# PR2019-DataAcquisitionSystem.net
KiCad netlist of a schematic drawn in Altium Designer
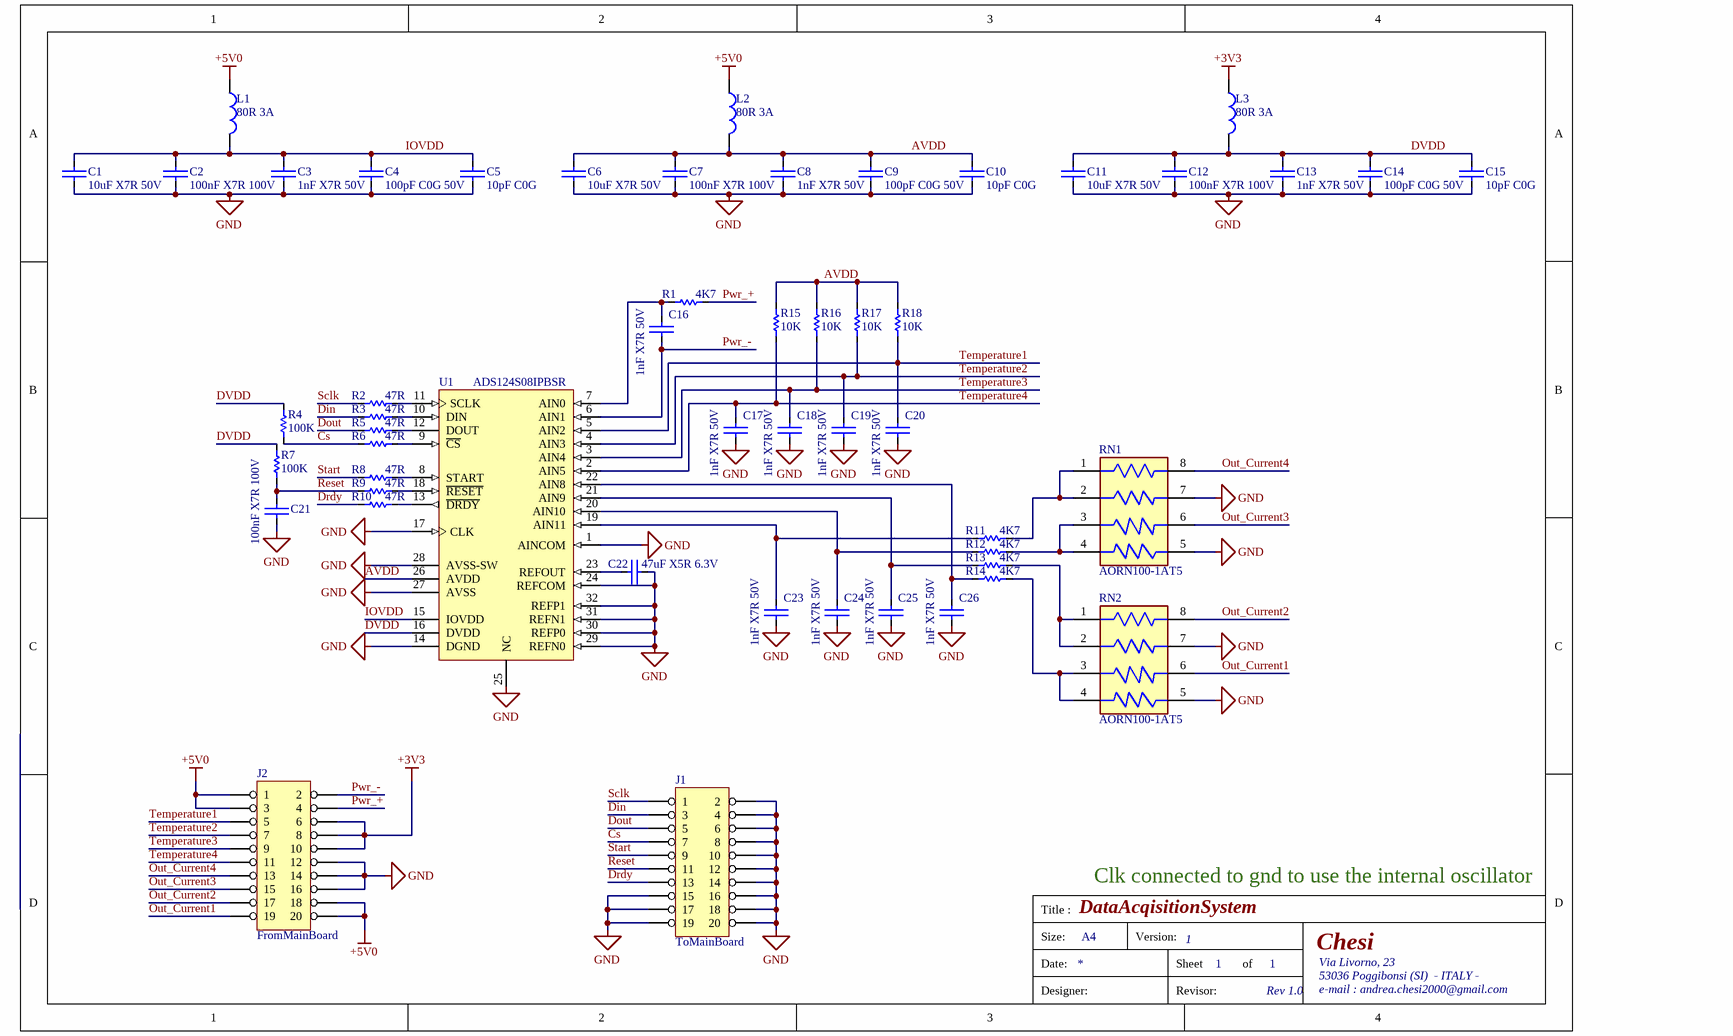
[diagram p0: PR2019-DataAcquisitionSystem.SchDoc]

(export (version "E")
  (design (tool "Eeschema 10.0.6"))
  (components
    (comp (ref "C1")
      (value "10uF X7R 50V")
      (footprint "1206")
      (description "Capacità")
      (fields
        (field (name "1 SUPPLIER PART NUMBER") "CL31B106KBHNNNE")
        (field (name "ARSILICII PART NUMBER") "CPC0232011")
      )
      (libsource (lib "Library_20-02-20") (part "CAP_10uF X7R 50V_1206"))
    )
    (comp (ref "C2")
      (value "100nF X7R 100V")
      (footprint "0805")
      (description "Capacità")
      (fields
        (field (name "1 SUPPLIER PART NUMBER") "CL21B104KCFSFNG")
        (field (name "2 SUPPLIER PART NUMBER") "1907331")
      )
      (libsource (lib "Library_20-02-20") (part "CAP_100nF X7R 100V_0805"))
    )
    (comp (ref "C3")
      (value "1nF X7R 50V")
      (footprint "0805")
      (description "Capacità")
      (fields
        (field (name "1 SUPPLIER PART NUMBER") "B37941K5102K60")
        (field (name "2 SUPPLIER PART NUMBER") "0805B102K5CT")
      )
      (libsource (lib "Library_20-02-20") (part "CAP_1nF X7R 50V_0805"))
    )
    (comp (ref "C4")
      (value "100pF C0G 50V")
      (footprint "0805")
      (description "Capacità")
      (fields
        (field (name "1 SUPPLIER PART NUMBER") "CC0805JRNPO9BN101")
        (field (name "ARSILICII PART NUMBER") "CPC0614100")
      )
      (libsource (lib "Library_20-02-20") (part "CAP_100pF C0G 50V_0805"))
    )
    (comp (ref "C5")
      (value "10pF C0G")
      (footprint "0805")
      (description "Capacità")
      (fields (field (name "ARSILICII PART NUMBER") "CPC0614010"))
      (libsource (lib "Library_20-02-20") (part "CAP_10pF C0G_0805"))
    )
    (comp (ref "C6")
      (value "10uF X7R 50V")
      (footprint "1206")
      (description "Capacità")
      (fields
        (field (name "1 SUPPLIER PART NUMBER") "CL31B106KBHNNNE")
        (field (name "ARSILICII PART NUMBER") "CPC0232011")
      )
      (libsource (lib "Library_20-02-20") (part "CAP_10uF X7R 50V_1206"))
    )
    (comp (ref "C7")
      (value "100nF X7R 100V")
      (footprint "0805")
      (description "Capacità")
      (fields
        (field (name "1 SUPPLIER PART NUMBER") "CL21B104KCFSFNG")
        (field (name "2 SUPPLIER PART NUMBER") "1907331")
      )
      (libsource (lib "Library_20-02-20") (part "CAP_100nF X7R 100V_0805"))
    )
    (comp (ref "C8")
      (value "1nF X7R 50V")
      (footprint "0805")
      (description "Capacità")
      (fields
        (field (name "1 SUPPLIER PART NUMBER") "B37941K5102K60")
        (field (name "2 SUPPLIER PART NUMBER") "0805B102K5CT")
      )
      (libsource (lib "Library_20-02-20") (part "CAP_1nF X7R 50V_0805"))
    )
    (comp (ref "C9")
      (value "100pF C0G 50V")
      (footprint "0805")
      (description "Capacità")
      (fields
        (field (name "1 SUPPLIER PART NUMBER") "CC0805JRNPO9BN101")
        (field (name "ARSILICII PART NUMBER") "CPC0614100")
      )
      (libsource (lib "Library_20-02-20") (part "CAP_100pF C0G 50V_0805"))
    )
    (comp (ref "C10")
      (value "10pF C0G")
      (footprint "0805")
      (description "Capacità")
      (fields (field (name "ARSILICII PART NUMBER") "CPC0614010"))
      (libsource (lib "Library_20-02-20") (part "CAP_10pF C0G_0805"))
    )
    (comp (ref "C11")
      (value "10uF X7R 50V")
      (footprint "1206")
      (description "Capacità")
      (fields
        (field (name "1 SUPPLIER PART NUMBER") "CL31B106KBHNNNE")
        (field (name "ARSILICII PART NUMBER") "CPC0232011")
      )
      (libsource (lib "Library_20-02-20") (part "CAP_10uF X7R 50V_1206"))
    )
    (comp (ref "C12")
      (value "100nF X7R 100V")
      (footprint "0805")
      (description "Capacità")
      (fields
        (field (name "1 SUPPLIER PART NUMBER") "CL21B104KCFSFNG")
        (field (name "2 SUPPLIER PART NUMBER") "1907331")
      )
      (libsource (lib "Library_20-02-20") (part "CAP_100nF X7R 100V_0805"))
    )
    (comp (ref "C13")
      (value "1nF X7R 50V")
      (footprint "0805")
      (description "Capacità")
      (fields
        (field (name "1 SUPPLIER PART NUMBER") "B37941K5102K60")
        (field (name "2 SUPPLIER PART NUMBER") "0805B102K5CT")
      )
      (libsource (lib "Library_20-02-20") (part "CAP_1nF X7R 50V_0805"))
    )
    (comp (ref "C14")
      (value "100pF C0G 50V")
      (footprint "0805")
      (description "Capacità")
      (fields
        (field (name "1 SUPPLIER PART NUMBER") "CC0805JRNPO9BN101")
        (field (name "ARSILICII PART NUMBER") "CPC0614100")
      )
      (libsource (lib "Library_20-02-20") (part "CAP_100pF C0G 50V_0805"))
    )
    (comp (ref "C15")
      (value "10pF C0G")
      (footprint "0805")
      (description "Capacità")
      (fields (field (name "ARSILICII PART NUMBER") "CPC0614010"))
      (libsource (lib "Library_20-02-20") (part "CAP_10pF C0G_0805"))
    )
    (comp (ref "C16")
      (value "1nF X7R 50V")
      (footprint "0805")
      (description "Capacità")
      (fields
        (field (name "1 SUPPLIER PART NUMBER") "B37941K5102K60")
        (field (name "2 SUPPLIER PART NUMBER") "0805B102K5CT")
      )
      (libsource (lib "Library_20-02-20") (part "CAP_1nF X7R 50V_0805"))
    )
    (comp (ref "C17")
      (value "1nF X7R 50V")
      (footprint "0805")
      (description "Capacità")
      (fields
        (field (name "1 SUPPLIER PART NUMBER") "B37941K5102K60")
        (field (name "2 SUPPLIER PART NUMBER") "0805B102K5CT")
      )
      (libsource (lib "Library_20-02-20") (part "CAP_1nF X7R 50V_0805"))
    )
    (comp (ref "C18")
      (value "1nF X7R 50V")
      (footprint "0805")
      (description "Capacità")
      (fields
        (field (name "1 SUPPLIER PART NUMBER") "B37941K5102K60")
        (field (name "2 SUPPLIER PART NUMBER") "0805B102K5CT")
      )
      (libsource (lib "Library_20-02-20") (part "CAP_1nF X7R 50V_0805"))
    )
    (comp (ref "C19")
      (value "1nF X7R 50V")
      (footprint "0805")
      (description "Capacità")
      (fields
        (field (name "1 SUPPLIER PART NUMBER") "B37941K5102K60")
        (field (name "2 SUPPLIER PART NUMBER") "0805B102K5CT")
      )
      (libsource (lib "Library_20-02-20") (part "CAP_1nF X7R 50V_0805"))
    )
    (comp (ref "C20")
      (value "1nF X7R 50V")
      (footprint "0805")
      (description "Capacità")
      (fields
        (field (name "1 SUPPLIER PART NUMBER") "B37941K5102K60")
        (field (name "2 SUPPLIER PART NUMBER") "0805B102K5CT")
      )
      (libsource (lib "Library_20-02-20") (part "CAP_1nF X7R 50V_0805"))
    )
    (comp (ref "C21")
      (value "100nF X7R 100V")
      (footprint "0805")
      (description "Capacità")
      (fields
        (field (name "1 SUPPLIER PART NUMBER") "CL21B104KCFSFNG")
        (field (name "2 SUPPLIER PART NUMBER") "1907331")
      )
      (libsource (lib "Library_20-02-20") (part "CAP_100nF X7R 100V_0805"))
    )
    (comp (ref "C22")
      (value "47uF X5R 6.3V")
      (footprint "0805")
      (description "Capacità")
      (fields
        (field (name "1 SUPPLIER PART NUMBER") "81-GRM21BR60J476ME5L")
        (field (name "2 SUPPLIER PART NUMBER") "846-7322")
      )
      (libsource (lib "Library_20-02-20") (part "CAP_47uF X5R 6.3V_0805"))
    )
    (comp (ref "C23")
      (value "1nF X7R 50V")
      (footprint "0805")
      (description "Capacità")
      (fields
        (field (name "1 SUPPLIER PART NUMBER") "B37941K5102K60")
        (field (name "2 SUPPLIER PART NUMBER") "0805B102K5CT")
      )
      (libsource (lib "Library_20-02-20") (part "CAP_1nF X7R 50V_0805"))
    )
    (comp (ref "C24")
      (value "1nF X7R 50V")
      (footprint "0805")
      (description "Capacità")
      (fields
        (field (name "1 SUPPLIER PART NUMBER") "B37941K5102K60")
        (field (name "2 SUPPLIER PART NUMBER") "0805B102K5CT")
      )
      (libsource (lib "Library_20-02-20") (part "CAP_1nF X7R 50V_0805"))
    )
    (comp (ref "C25")
      (value "1nF X7R 50V")
      (footprint "0805")
      (description "Capacità")
      (fields
        (field (name "1 SUPPLIER PART NUMBER") "B37941K5102K60")
        (field (name "2 SUPPLIER PART NUMBER") "0805B102K5CT")
      )
      (libsource (lib "Library_20-02-20") (part "CAP_1nF X7R 50V_0805"))
    )
    (comp (ref "C26")
      (value "1nF X7R 50V")
      (footprint "0805")
      (description "Capacità")
      (fields
        (field (name "1 SUPPLIER PART NUMBER") "B37941K5102K60")
        (field (name "2 SUPPLIER PART NUMBER") "0805B102K5CT")
      )
      (libsource (lib "Library_20-02-20") (part "CAP_1nF X7R 50V_0805"))
    )
    (comp (ref "J1")
      (value "ToMainBoard")
      (footprint "IDC-20")
      (libsource (lib "Library_20-02-20") (part "HEADER 10X2"))
    )
    (comp (ref "J2")
      (value "FromMainBoard")
      (footprint "IDC-20")
      (libsource (lib "Library_20-02-20") (part "HEADER 10X2"))
    )
    (comp (ref "L1")
      (value "80R 3A")
      (footprint "1206")
      (description "Ferrite")
      (fields
        (field (name "1 SUPPLIER PART NUMBER") "3275550P")
        (field (name "ARSILICII PART NUMBER") "CPF0006000")
      )
      (libsource (lib "Library_20-02-20") (part "Ferrite 80R 3A"))
    )
    (comp (ref "L2")
      (value "80R 3A")
      (footprint "1206")
      (description "Ferrite")
      (fields
        (field (name "1 SUPPLIER PART NUMBER") "3275550P")
        (field (name "ARSILICII PART NUMBER") "CPF0006000")
      )
      (libsource (lib "Library_20-02-20") (part "Ferrite 80R 3A"))
    )
    (comp (ref "L3")
      (value "80R 3A")
      (footprint "1206")
      (description "Ferrite")
      (fields
        (field (name "1 SUPPLIER PART NUMBER") "3275550P")
        (field (name "ARSILICII PART NUMBER") "CPF0006000")
      )
      (libsource (lib "Library_20-02-20") (part "Ferrite 80R 3A"))
    )
    (comp (ref "R1")
      (value "4K7")
      (footprint "0805")
      (description "Resistenza")
      (libsource (lib "Library_20-02-20") (part "RES_SMD"))
    )
    (comp (ref "R2")
      (value "47R")
      (footprint "0805")
      (description "Resistenza")
      (libsource (lib "Library_20-02-20") (part "RES_SMD"))
    )
    (comp (ref "R3")
      (value "47R")
      (footprint "0805")
      (description "Resistenza")
      (libsource (lib "Library_20-02-20") (part "RES_SMD"))
    )
    (comp (ref "R4")
      (value "100K")
      (footprint "0805")
      (description "Resistenza")
      (libsource (lib "Library_20-02-20") (part "RES_SMD"))
    )
    (comp (ref "R5")
      (value "47R")
      (footprint "0805")
      (description "Resistenza")
      (libsource (lib "Library_20-02-20") (part "RES_SMD"))
    )
    (comp (ref "R6")
      (value "47R")
      (footprint "0805")
      (description "Resistenza")
      (libsource (lib "Library_20-02-20") (part "RES_SMD"))
    )
    (comp (ref "R7")
      (value "100K")
      (footprint "0805")
      (description "Resistenza")
      (libsource (lib "Library_20-02-20") (part "RES_SMD"))
    )
    (comp (ref "R8")
      (value "47R")
      (footprint "0805")
      (description "Resistenza")
      (libsource (lib "Library_20-02-20") (part "RES_SMD"))
    )
    (comp (ref "R9")
      (value "47R")
      (footprint "0805")
      (description "Resistenza")
      (libsource (lib "Library_20-02-20") (part "RES_SMD"))
    )
    (comp (ref "R10")
      (value "47R")
      (footprint "0805")
      (description "Resistenza")
      (libsource (lib "Library_20-02-20") (part "RES_SMD"))
    )
    (comp (ref "R11")
      (value "4K7")
      (footprint "0805")
      (description "Resistenza")
      (libsource (lib "Library_20-02-20") (part "RES_SMD"))
    )
    (comp (ref "R12")
      (value "4K7")
      (footprint "0805")
      (description "Resistenza")
      (libsource (lib "Library_20-02-20") (part "RES_SMD"))
    )
    (comp (ref "R13")
      (value "4K7")
      (footprint "0805")
      (description "Resistenza")
      (libsource (lib "Library_20-02-20") (part "RES_SMD"))
    )
    (comp (ref "R14")
      (value "4K7")
      (footprint "0805")
      (description "Resistenza")
      (libsource (lib "Library_20-02-20") (part "RES_SMD"))
    )
    (comp (ref "R15")
      (value "10K")
      (footprint "0805")
      (description "Resistenza")
      (libsource (lib "Library_20-02-20") (part "RES_SMD"))
    )
    (comp (ref "R16")
      (value "10K")
      (footprint "0805")
      (description "Resistenza")
      (libsource (lib "Library_20-02-20") (part "RES_SMD"))
    )
    (comp (ref "R17")
      (value "10K")
      (footprint "0805")
      (description "Resistenza")
      (libsource (lib "Library_20-02-20") (part "RES_SMD"))
    )
    (comp (ref "R18")
      (value "10K")
      (footprint "0805")
      (description "Resistenza")
      (libsource (lib "Library_20-02-20") (part "RES_SMD"))
    )
    (comp (ref "RN1")
      (value "AORN100-1AT5")
      (footprint "FP-AORN100-1AT5-IPC_C")
      (description "RES NETWORK 4 RES MULT OHM 8SOIC")
      (fields (field (name "MANUFACTURER") "Vishay") (field (name "TOLERANCE") "0.1%"))
      (libsource (lib "Altium Content Vault") (part "8441eaa576eb2593bca60d5301712c1"))
    )
    (comp (ref "RN2")
      (value "AORN100-1AT5")
      (footprint "FP-AORN100-1AT5-IPC_C")
      (description "RES NETWORK 4 RES MULT OHM 8SOIC")
      (fields (field (name "MANUFACTURER") "Vishay") (field (name "TOLERANCE") "0.1%"))
      (libsource (lib "Altium Content Vault") (part "8441eaa576eb2593bca60d5301712c1"))
    )
    (comp (ref "U1")
      (value "ADS124S08IPBSR")
      (footprint "LQFP-32_N")
      (libsource (lib "Library_20-02-20") (part "ADS124S08IPBSR"))
    )
  )
  (nets
    (net (code "1") (name "+3V3") (class "Default")
      (node (ref "J2") (pin "10") (pinfunction "10_10") (pintype "passive"))
      (node (ref "J2") (pin "6") (pinfunction "6_6") (pintype "passive"))
      (node (ref "J2") (pin "8") (pinfunction "8_8") (pintype "passive"))
      (node (ref "L3") (pin "1") (pinfunction "1_1") (pintype "passive"))
    )
    (net (code "2") (name "+5V0") (class "Default")
      (node (ref "J2") (pin "1") (pinfunction "1_1") (pintype "passive"))
      (node (ref "J2") (pin "18") (pinfunction "18_18") (pintype "passive"))
      (node (ref "J2") (pin "20") (pinfunction "20_20") (pintype "passive"))
      (node (ref "J2") (pin "3") (pinfunction "3_3") (pintype "passive"))
      (node (ref "L1") (pin "1") (pinfunction "1_1") (pintype "passive"))
      (node (ref "L2") (pin "1") (pinfunction "1_1") (pintype "passive"))
    )
    (net (code "3") (name "/AVDD") (class "Default")
      (node (ref "C10") (pin "1") (pintype "passive"))
      (node (ref "C6") (pin "1") (pintype "passive"))
      (node (ref "C7") (pin "1") (pintype "passive"))
      (node (ref "C8") (pin "1") (pintype "passive"))
      (node (ref "C9") (pin "1") (pintype "passive"))
      (node (ref "L2") (pin "2") (pinfunction "2_2") (pintype "passive"))
      (node (ref "R15") (pin "1") (pinfunction "1_1") (pintype "passive"))
      (node (ref "R16") (pin "1") (pinfunction "1_1") (pintype "passive"))
      (node (ref "R17") (pin "1") (pinfunction "1_1") (pintype "passive"))
      (node (ref "R18") (pin "1") (pinfunction "1_1") (pintype "passive"))
      (node (ref "U1") (pin "26") (pinfunction "AVDD_26") (pintype "power_in"))
    )
    (net (code "4") (name "/Cs") (class "Default")
      (node (ref "J1") (pin "7") (pinfunction "7_7") (pintype "passive"))
      (node (ref "R4") (pin "2") (pinfunction "2_2") (pintype "passive"))
      (node (ref "R6") (pin "2") (pinfunction "2_2") (pintype "passive"))
    )
    (net (code "5") (name "/DVDD") (class "Default")
      (node (ref "C11") (pin "1") (pintype "passive"))
      (node (ref "C12") (pin "1") (pintype "passive"))
      (node (ref "C13") (pin "1") (pintype "passive"))
      (node (ref "C14") (pin "1") (pintype "passive"))
      (node (ref "C15") (pin "1") (pintype "passive"))
      (node (ref "L3") (pin "2") (pinfunction "2_2") (pintype "passive"))
      (node (ref "R4") (pin "1") (pinfunction "1_1") (pintype "passive"))
      (node (ref "R7") (pin "1") (pinfunction "1_1") (pintype "passive"))
      (node (ref "U1") (pin "16") (pinfunction "DVDD_16") (pintype "power_in"))
    )
    (net (code "6") (name "/Din") (class "Default")
      (node (ref "J1") (pin "3") (pinfunction "3_3") (pintype "passive"))
      (node (ref "R3") (pin "2") (pinfunction "2_2") (pintype "passive"))
    )
    (net (code "7") (name "/Dout") (class "Default")
      (node (ref "J1") (pin "5") (pinfunction "5_5") (pintype "passive"))
      (node (ref "R5") (pin "2") (pinfunction "2_2") (pintype "passive"))
    )
    (net (code "8") (name "/Drdy") (class "Default")
      (node (ref "J1") (pin "13") (pinfunction "13_13") (pintype "passive"))
      (node (ref "R10") (pin "2") (pinfunction "2_2") (pintype "passive"))
    )
    (net (code "9") (name "/IOVDD") (class "Default")
      (node (ref "C1") (pin "1") (pintype "passive"))
      (node (ref "C2") (pin "1") (pintype "passive"))
      (node (ref "C3") (pin "1") (pintype "passive"))
      (node (ref "C4") (pin "1") (pintype "passive"))
      (node (ref "C5") (pin "1") (pintype "passive"))
      (node (ref "L1") (pin "2") (pinfunction "2_2") (pintype "passive"))
      (node (ref "U1") (pin "15") (pinfunction "IOVDD_15") (pintype "power_in"))
    )
    (net (code "10") (name "/Out_Current1") (class "Default")
      (node (ref "J2") (pin "19") (pinfunction "19_19") (pintype "passive"))
      (node (ref "RN2") (pin "6") (pinfunction "6_6") (pintype "passive"))
    )
    (net (code "11") (name "/Out_Current2") (class "Default")
      (node (ref "J2") (pin "17") (pinfunction "17_17") (pintype "passive"))
      (node (ref "RN2") (pin "8") (pinfunction "8_8") (pintype "passive"))
    )
    (net (code "12") (name "/Out_Current3") (class "Default")
      (node (ref "J2") (pin "15") (pinfunction "15_15") (pintype "passive"))
      (node (ref "RN1") (pin "6") (pinfunction "6_6") (pintype "passive"))
    )
    (net (code "13") (name "/Out_Current4") (class "Default")
      (node (ref "J2") (pin "13") (pinfunction "13_13") (pintype "passive"))
      (node (ref "RN1") (pin "8") (pinfunction "8_8") (pintype "passive"))
    )
    (net (code "14") (name "/Pwr_+") (class "Default")
      (node (ref "J2") (pin "4") (pinfunction "4_4") (pintype "passive"))
      (node (ref "R1") (pin "1") (pinfunction "1_1") (pintype "passive"))
    )
    (net (code "15") (name "/Pwr_-") (class "Default")
      (node (ref "C16") (pin "2") (pintype "passive"))
      (node (ref "J2") (pin "2") (pinfunction "2_2") (pintype "passive"))
      (node (ref "U1") (pin "6") (pinfunction "AIN1_6") (pintype "input"))
    )
    (net (code "16") (name "/Reset") (class "Default")
      (node (ref "C21") (pin "1") (pintype "passive"))
      (node (ref "J1") (pin "11") (pinfunction "11_11") (pintype "passive"))
      (node (ref "R7") (pin "2") (pinfunction "2_2") (pintype "passive"))
      (node (ref "R9") (pin "2") (pinfunction "2_2") (pintype "passive"))
    )
    (net (code "17") (name "/Sclk") (class "Default")
      (node (ref "J1") (pin "1") (pinfunction "1_1") (pintype "passive"))
      (node (ref "R2") (pin "2") (pinfunction "2_2") (pintype "passive"))
    )
    (net (code "18") (name "/Start") (class "Default")
      (node (ref "J1") (pin "9") (pinfunction "9_9") (pintype "passive"))
      (node (ref "R8") (pin "2") (pinfunction "2_2") (pintype "passive"))
    )
    (net (code "19") (name "/Temperature1") (class "Default")
      (node (ref "C20") (pin "1") (pintype "passive"))
      (node (ref "J2") (pin "5") (pinfunction "5_5") (pintype "passive"))
      (node (ref "R18") (pin "2") (pinfunction "2_2") (pintype "passive"))
      (node (ref "U1") (pin "5") (pinfunction "AIN2_5") (pintype "input"))
    )
    (net (code "20") (name "/Temperature2") (class "Default")
      (node (ref "C19") (pin "1") (pintype "passive"))
      (node (ref "J2") (pin "7") (pinfunction "7_7") (pintype "passive"))
      (node (ref "R17") (pin "2") (pinfunction "2_2") (pintype "passive"))
      (node (ref "U1") (pin "4") (pinfunction "AIN3_4") (pintype "input"))
    )
    (net (code "21") (name "/Temperature3") (class "Default")
      (node (ref "C18") (pin "1") (pintype "passive"))
      (node (ref "J2") (pin "9") (pinfunction "9_9") (pintype "passive"))
      (node (ref "R16") (pin "2") (pinfunction "2_2") (pintype "passive"))
      (node (ref "U1") (pin "3") (pinfunction "AIN4_3") (pintype "input"))
    )
    (net (code "22") (name "/Temperature4") (class "Default")
      (node (ref "C17") (pin "1") (pintype "passive"))
      (node (ref "J2") (pin "11") (pinfunction "11_11") (pintype "passive"))
      (node (ref "R15") (pin "2") (pinfunction "2_2") (pintype "passive"))
      (node (ref "U1") (pin "2") (pinfunction "AIN5_2") (pintype "input"))
    )
    (net (code "23") (name "GND") (class "Default")
      (node (ref "C1") (pin "2") (pintype "passive"))
      (node (ref "C10") (pin "2") (pintype "passive"))
      (node (ref "C11") (pin "2") (pintype "passive"))
      (node (ref "C12") (pin "2") (pintype "passive"))
      (node (ref "C13") (pin "2") (pintype "passive"))
      (node (ref "C14") (pin "2") (pintype "passive"))
      (node (ref "C15") (pin "2") (pintype "passive"))
      (node (ref "C17") (pin "2") (pintype "passive"))
      (node (ref "C18") (pin "2") (pintype "passive"))
      (node (ref "C19") (pin "2") (pintype "passive"))
      (node (ref "C2") (pin "2") (pintype "passive"))
      (node (ref "C20") (pin "2") (pintype "passive"))
      (node (ref "C21") (pin "2") (pintype "passive"))
      (node (ref "C22") (pin "2") (pintype "passive"))
      (node (ref "C23") (pin "2") (pintype "passive"))
      (node (ref "C24") (pin "2") (pintype "passive"))
      (node (ref "C25") (pin "2") (pintype "passive"))
      (node (ref "C26") (pin "2") (pintype "passive"))
      (node (ref "C3") (pin "2") (pintype "passive"))
      (node (ref "C4") (pin "2") (pintype "passive"))
      (node (ref "C5") (pin "2") (pintype "passive"))
      (node (ref "C6") (pin "2") (pintype "passive"))
      (node (ref "C7") (pin "2") (pintype "passive"))
      (node (ref "C8") (pin "2") (pintype "passive"))
      (node (ref "C9") (pin "2") (pintype "passive"))
      (node (ref "J1") (pin "10") (pinfunction "10_10") (pintype "passive"))
      (node (ref "J1") (pin "12") (pinfunction "12_12") (pintype "passive"))
      (node (ref "J1") (pin "14") (pinfunction "14_14") (pintype "passive"))
      (node (ref "J1") (pin "15") (pinfunction "15_15") (pintype "passive"))
      (node (ref "J1") (pin "16") (pinfunction "16_16") (pintype "passive"))
      (node (ref "J1") (pin "17") (pinfunction "17_17") (pintype "passive"))
      (node (ref "J1") (pin "18") (pinfunction "18_18") (pintype "passive"))
      (node (ref "J1") (pin "19") (pinfunction "19_19") (pintype "passive"))
      (node (ref "J1") (pin "2") (pinfunction "2_2") (pintype "passive"))
      (node (ref "J1") (pin "20") (pinfunction "20_20") (pintype "passive"))
      (node (ref "J1") (pin "4") (pinfunction "4_4") (pintype "passive"))
      (node (ref "J1") (pin "6") (pinfunction "6_6") (pintype "passive"))
      (node (ref "J1") (pin "8") (pinfunction "8_8") (pintype "passive"))
      (node (ref "J2") (pin "12") (pinfunction "12_12") (pintype "passive"))
      (node (ref "J2") (pin "14") (pinfunction "14_14") (pintype "passive"))
      (node (ref "J2") (pin "16") (pinfunction "16_16") (pintype "passive"))
      (node (ref "RN1") (pin "5") (pinfunction "5_5") (pintype "passive"))
      (node (ref "RN1") (pin "7") (pinfunction "7_7") (pintype "passive"))
      (node (ref "RN2") (pin "5") (pinfunction "5_5") (pintype "passive"))
      (node (ref "RN2") (pin "7") (pinfunction "7_7") (pintype "passive"))
      (node (ref "U1") (pin "1") (pinfunction "AINCOM_1") (pintype "input"))
      (node (ref "U1") (pin "14") (pinfunction "DGND_14") (pintype "power_in"))
      (node (ref "U1") (pin "17") (pinfunction "CLK_17") (pintype "input"))
      (node (ref "U1") (pin "24") (pinfunction "REFCOM_24") (pintype "input"))
      (node (ref "U1") (pin "25") (pinfunction "NC_25") (pintype "power_in"))
      (node (ref "U1") (pin "27") (pinfunction "AVSS_27") (pintype "power_in"))
      (node (ref "U1") (pin "28") (pinfunction "AVSS-SW_28") (pintype "power_in"))
      (node (ref "U1") (pin "29") (pinfunction "REFN0_29") (pintype "input"))
      (node (ref "U1") (pin "30") (pinfunction "REFP0_30") (pintype "input"))
      (node (ref "U1") (pin "31") (pinfunction "REFN1_31") (pintype "input"))
      (node (ref "U1") (pin "32") (pinfunction "REFP1_32") (pintype "input"))
    )
    (net (code "24") (name "Net-(R11-Pad1)") (class "Default")
      (node (ref "R11") (pin "1") (pinfunction "1_1") (pintype "passive"))
      (node (ref "RN1") (pin "1") (pinfunction "1_1") (pintype "passive"))
      (node (ref "RN1") (pin "2") (pinfunction "2_2") (pintype "passive"))
    )
    (net (code "25") (name "Net-(R12-Pad1)") (class "Default")
      (node (ref "R12") (pin "1") (pinfunction "1_1") (pintype "passive"))
      (node (ref "RN1") (pin "3") (pinfunction "3_3") (pintype "passive"))
      (node (ref "RN1") (pin "4") (pinfunction "4_4") (pintype "passive"))
    )
    (net (code "26") (name "Net-(R13-Pad1)") (class "Default")
      (node (ref "R13") (pin "1") (pinfunction "1_1") (pintype "passive"))
      (node (ref "RN2") (pin "1") (pinfunction "1_1") (pintype "passive"))
      (node (ref "RN2") (pin "2") (pinfunction "2_2") (pintype "passive"))
    )
    (net (code "27") (name "Net-(R14-Pad1)") (class "Default")
      (node (ref "R14") (pin "1") (pinfunction "1_1") (pintype "passive"))
      (node (ref "RN2") (pin "3") (pinfunction "3_3") (pintype "passive"))
      (node (ref "RN2") (pin "4") (pinfunction "4_4") (pintype "passive"))
    )
    (net (code "28") (name "Net-(U1-AIN0)") (class "Default")
      (node (ref "C16") (pin "1") (pintype "passive"))
      (node (ref "R1") (pin "2") (pinfunction "2_2") (pintype "passive"))
      (node (ref "U1") (pin "7") (pinfunction "AIN0_7") (pintype "input"))
    )
    (net (code "29") (name "Net-(U1-AIN8)") (class "Default")
      (node (ref "C26") (pin "1") (pintype "passive"))
      (node (ref "R14") (pin "2") (pinfunction "2_2") (pintype "passive"))
      (node (ref "U1") (pin "22") (pinfunction "AIN8_22") (pintype "input"))
    )
    (net (code "30") (name "Net-(U1-AIN9)") (class "Default")
      (node (ref "C25") (pin "1") (pintype "passive"))
      (node (ref "R13") (pin "2") (pinfunction "2_2") (pintype "passive"))
      (node (ref "U1") (pin "21") (pinfunction "AIN9_21") (pintype "input"))
    )
    (net (code "31") (name "Net-(U1-AIN10)") (class "Default")
      (node (ref "C24") (pin "1") (pintype "passive"))
      (node (ref "R12") (pin "2") (pinfunction "2_2") (pintype "passive"))
      (node (ref "U1") (pin "20") (pinfunction "AIN10_20") (pintype "input"))
    )
    (net (code "32") (name "Net-(U1-AIN11)") (class "Default")
      (node (ref "C23") (pin "1") (pintype "passive"))
      (node (ref "R11") (pin "2") (pinfunction "2_2") (pintype "passive"))
      (node (ref "U1") (pin "19") (pinfunction "AIN11_19") (pintype "input"))
    )
    (net (code "33") (name "Net-(U1-DIN)") (class "Default")
      (node (ref "R3") (pin "1") (pinfunction "1_1") (pintype "passive"))
      (node (ref "U1") (pin "10") (pinfunction "DIN_10") (pintype "input"))
    )
    (net (code "34") (name "Net-(U1-DOUT)") (class "Default")
      (node (ref "R5") (pin "1") (pinfunction "1_1") (pintype "passive"))
      (node (ref "U1") (pin "12") (pinfunction "DOUT_12") (pintype "tri_state"))
    )
    (net (code "35") (name "Net-(U1-REFOUT)") (class "Default")
      (node (ref "C22") (pin "1") (pintype "passive"))
      (node (ref "U1") (pin "23") (pinfunction "REFOUT_23") (pintype "input"))
    )
    (net (code "36") (name "Net-(U1-SCLK)") (class "Default")
      (node (ref "R2") (pin "1") (pinfunction "1_1") (pintype "passive"))
      (node (ref "U1") (pin "11") (pinfunction "SCLK_11") (pintype "input"))
    )
    (net (code "37") (name "Net-(U1-START)") (class "Default")
      (node (ref "R8") (pin "1") (pinfunction "1_1") (pintype "passive"))
      (node (ref "U1") (pin "8") (pinfunction "START_8") (pintype "input"))
    )
    (net (code "38") (name "Net-(U1-~{CS})") (class "Default")
      (node (ref "R6") (pin "1") (pinfunction "1_1") (pintype "passive"))
      (node (ref "U1") (pin "9") (pinfunction "~{CS}_9") (pintype "input"))
    )
    (net (code "39") (name "Net-(U1-~{DRDY})") (class "Default")
      (node (ref "R10") (pin "1") (pinfunction "1_1") (pintype "passive"))
      (node (ref "U1") (pin "13") (pinfunction "~{DRDY}_13") (pintype "output"))
    )
    (net (code "40") (name "Net-(U1-~{RESET})") (class "Default")
      (node (ref "R9") (pin "1") (pinfunction "1_1") (pintype "passive"))
      (node (ref "U1") (pin "18") (pinfunction "~{RESET}_18") (pintype "input"))
    )
  )
)
